# lab3.net
KiCad netlist of a schematic drawn in EAGLE
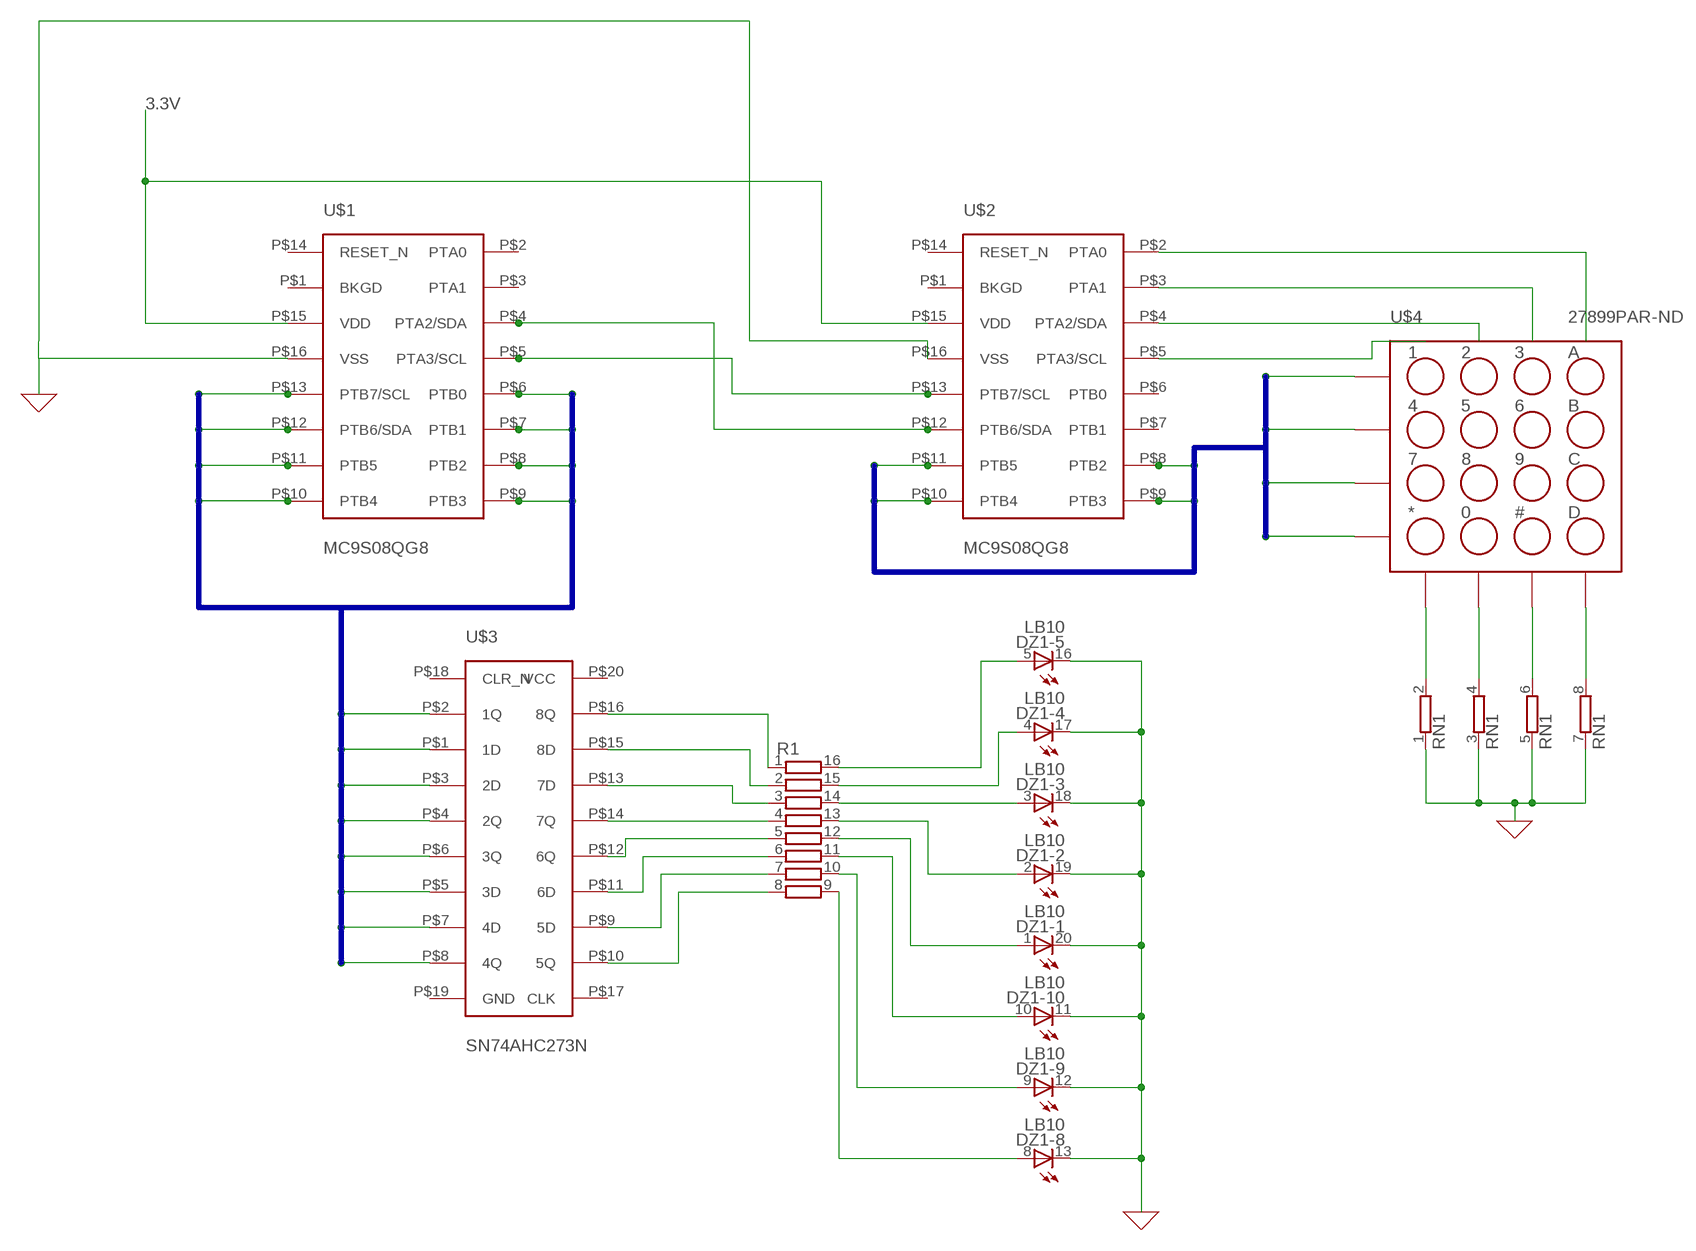
[diagram p0: schematic, sheet 1]

(export (version "E")
  (design (tool "Eeschema 10.0.6"))
  (components
    (comp (ref "DZ1")
      (value "LB10")
      (footprint "eagle-import:LB10")
      (libsource (lib "eagle-import") (part "LB10"))
    )
    (comp (ref "R1")
      (value "2QSP16-8")
      (footprint "eagle-import:2QSP16")
      (libsource (lib "eagle-import") (part "2QSP16-8"))
    )
    (comp (ref "RN1")
      (value "E4RP")
      (footprint "eagle-import:SIL8")
      (libsource (lib "eagle-import") (part "E4RP"))
    )
    (comp (ref "U$1")
      (value "MC9S08QG8")
      (footprint "eagle-import:MC9S08QG8")
      (libsource (lib "eagle-import") (part "MC9S08QG8"))
    )
    (comp (ref "U$2")
      (value "MC9S08QG8")
      (footprint "eagle-import:MC9S08QG8")
      (libsource (lib "eagle-import") (part "MC9S08QG8"))
    )
    (comp (ref "U$3")
      (value "SN74AHC273N")
      (footprint "eagle-import:SN74AHC273N")
      (libsource (lib "eagle-import") (part "SN74AHC273N"))
    )
    (comp (ref "U$4")
      (value "27899PAR-ND")
      (footprint "eagle-import:27899PAR-ND")
      (libsource (lib "eagle-import") (part "27899PAR-ND"))
    )
  )
  (nets
    (net (code "1") (name "/3.3V") (class "Default")
      (node (ref "U$1") (pin "P$15") (pinfunction "VDD_P$15") (pintype "bidirectional"))
      (node (ref "U$2") (pin "P$15") (pinfunction "VDD_P$15") (pintype "bidirectional"))
    )
    (net (code "2") (name "GND") (class "Default")
      (node (ref "DZ1") (pin "11") (pinfunction "C_11") (pintype "passive"))
      (node (ref "DZ1") (pin "12") (pinfunction "C_12") (pintype "passive"))
      (node (ref "DZ1") (pin "13") (pinfunction "C_13") (pintype "passive"))
      (node (ref "DZ1") (pin "16") (pinfunction "C_16") (pintype "passive"))
      (node (ref "DZ1") (pin "17") (pinfunction "C_17") (pintype "passive"))
      (node (ref "DZ1") (pin "18") (pinfunction "C_18") (pintype "passive"))
      (node (ref "DZ1") (pin "19") (pinfunction "C_19") (pintype "passive"))
      (node (ref "DZ1") (pin "20") (pinfunction "C_20") (pintype "passive"))
      (node (ref "RN1") (pin "1") (pinfunction "1_1") (pintype "passive"))
      (node (ref "RN1") (pin "3") (pinfunction "1_3") (pintype "passive"))
      (node (ref "RN1") (pin "5") (pinfunction "1_5") (pintype "passive"))
      (node (ref "RN1") (pin "7") (pinfunction "1_7") (pintype "passive"))
      (node (ref "U$1") (pin "P$16") (pinfunction "VSS_P$16") (pintype "bidirectional"))
      (node (ref "U$2") (pin "P$16") (pinfunction "VSS_P$16") (pintype "bidirectional"))
    )
    (net (code "3") (name "Net-(DZ1A-A)") (class "Default")
      (node (ref "DZ1") (pin "1") (pinfunction "A_1") (pintype "passive"))
      (node (ref "R1") (pin "12") (pinfunction "12_12") (pintype "passive"))
    )
    (net (code "4") (name "Net-(DZ1B-A)") (class "Default")
      (node (ref "DZ1") (pin "10") (pinfunction "A_10") (pintype "passive"))
      (node (ref "R1") (pin "11") (pinfunction "11_11") (pintype "passive"))
    )
    (net (code "5") (name "Net-(DZ1C-A)") (class "Default")
      (node (ref "DZ1") (pin "2") (pinfunction "A_2") (pintype "passive"))
      (node (ref "R1") (pin "13") (pinfunction "13_13") (pintype "passive"))
    )
    (net (code "6") (name "Net-(DZ1D-A)") (class "Default")
      (node (ref "DZ1") (pin "3") (pinfunction "A_3") (pintype "passive"))
      (node (ref "R1") (pin "14") (pinfunction "14_14") (pintype "passive"))
    )
    (net (code "7") (name "Net-(DZ1E-A)") (class "Default")
      (node (ref "DZ1") (pin "4") (pinfunction "A_4") (pintype "passive"))
      (node (ref "R1") (pin "15") (pinfunction "15_15") (pintype "passive"))
    )
    (net (code "8") (name "Net-(DZ1F-A)") (class "Default")
      (node (ref "DZ1") (pin "5") (pinfunction "A_5") (pintype "passive"))
      (node (ref "R1") (pin "16") (pinfunction "16_16") (pintype "passive"))
    )
    (net (code "9") (name "Net-(DZ1I-A)") (class "Default")
      (node (ref "DZ1") (pin "8") (pinfunction "A_8") (pintype "passive"))
      (node (ref "R1") (pin "9") (pinfunction "9_9") (pintype "passive"))
    )
    (net (code "10") (name "Net-(DZ1J-A)") (class "Default")
      (node (ref "DZ1") (pin "9") (pinfunction "A_9") (pintype "passive"))
      (node (ref "R1") (pin "10") (pinfunction "10_10") (pintype "passive"))
    )
    (net (code "11") (name "Net-(RN1-Pad2)") (class "Default")
      (node (ref "RN1") (pin "2") (pinfunction "2_2") (pintype "passive"))
      (node (ref "U$4") (pin "P$8") (pinfunction "P$8_P$8") (pintype "bidirectional"))
    )
    (net (code "12") (name "Net-(RN1B-2)") (class "Default")
      (node (ref "RN1") (pin "4") (pinfunction "2_4") (pintype "passive"))
      (node (ref "U$4") (pin "P$7") (pinfunction "P$7_P$7") (pintype "bidirectional"))
    )
    (net (code "13") (name "Net-(RN1C-2)") (class "Default")
      (node (ref "RN1") (pin "6") (pinfunction "2_6") (pintype "passive"))
      (node (ref "U$4") (pin "P$6") (pinfunction "P$6_P$6") (pintype "bidirectional"))
    )
    (net (code "14") (name "Net-(RN1D-2)") (class "Default")
      (node (ref "RN1") (pin "8") (pinfunction "2_8") (pintype "passive"))
      (node (ref "U$4") (pin "P$5") (pinfunction "P$5_P$5") (pintype "bidirectional"))
    )
    (net (code "15") (name "Net-(U$1-PTA2{slash}SDA)") (class "Default")
      (node (ref "U$1") (pin "P$4") (pinfunction "PTA2/SDA_P$4") (pintype "bidirectional"))
      (node (ref "U$2") (pin "P$12") (pinfunction "PTB6/SDA_P$12") (pintype "bidirectional"))
    )
    (net (code "16") (name "Net-(U$1-PTA3{slash}SCL)") (class "Default")
      (node (ref "U$1") (pin "P$5") (pinfunction "PTA3/SCL_P$5") (pintype "bidirectional"))
      (node (ref "U$2") (pin "P$13") (pinfunction "PTB7/SCL_P$13") (pintype "bidirectional"))
    )
    (net (code "17") (name "Net-(U$3-5D)") (class "Default")
      (node (ref "R1") (pin "7") (pinfunction "7_7") (pintype "passive"))
      (node (ref "U$3") (pin "P$9") (pinfunction "5D_P$9") (pintype "bidirectional"))
    )
    (net (code "18") (name "Net-(U$3-5Q)") (class "Default")
      (node (ref "R1") (pin "8") (pinfunction "8_8") (pintype "passive"))
      (node (ref "U$3") (pin "P$10") (pinfunction "5Q_P$10") (pintype "bidirectional"))
    )
    (net (code "19") (name "Net-(U$3-6D)") (class "Default")
      (node (ref "R1") (pin "6") (pinfunction "6_6") (pintype "passive"))
      (node (ref "U$3") (pin "P$11") (pinfunction "6D_P$11") (pintype "bidirectional"))
    )
    (net (code "20") (name "Net-(U$3-6Q)") (class "Default")
      (node (ref "R1") (pin "5") (pinfunction "5_5") (pintype "passive"))
      (node (ref "U$3") (pin "P$12") (pinfunction "6Q_P$12") (pintype "bidirectional"))
    )
    (net (code "21") (name "Net-(U$3-7D)") (class "Default")
      (node (ref "R1") (pin "3") (pinfunction "3_3") (pintype "passive"))
      (node (ref "U$3") (pin "P$13") (pinfunction "7D_P$13") (pintype "bidirectional"))
    )
    (net (code "22") (name "Net-(U$3-7Q)") (class "Default")
      (node (ref "R1") (pin "4") (pinfunction "4_4") (pintype "passive"))
      (node (ref "U$3") (pin "P$14") (pinfunction "7Q_P$14") (pintype "bidirectional"))
    )
    (net (code "23") (name "Net-(U$3-8D)") (class "Default")
      (node (ref "R1") (pin "2") (pinfunction "2_2") (pintype "passive"))
      (node (ref "U$3") (pin "P$15") (pinfunction "8D_P$15") (pintype "bidirectional"))
    )
    (net (code "24") (name "Net-(U$3-8Q)") (class "Default")
      (node (ref "R1") (pin "1") (pinfunction "1_1") (pintype "passive"))
      (node (ref "U$3") (pin "P$16") (pinfunction "8Q_P$16") (pintype "bidirectional"))
    )
    (net (code "25") (name "unconnected-(U$1-BKGD-PadP$1)") (class "Default")
      (node (ref "U$1") (pin "P$1") (pinfunction "BKGD_P$1") (pintype "bidirectional"))
    )
    (net (code "26") (name "unconnected-(U$1-PTA0-PadP$2)") (class "Default")
      (node (ref "U$1") (pin "P$2") (pinfunction "PTA0_P$2") (pintype "bidirectional"))
    )
    (net (code "27") (name "unconnected-(U$1-PTA1-PadP$3)") (class "Default")
      (node (ref "U$1") (pin "P$3") (pinfunction "PTA1_P$3") (pintype "bidirectional"))
    )
    (net (code "28") (name "unconnected-(U$1-PTB0-PadP$6)") (class "Default")
      (node (ref "U$1") (pin "P$6") (pinfunction "PTB0_P$6") (pintype "bidirectional"))
    )
    (net (code "29") (name "unconnected-(U$1-PTB1-PadP$7)") (class "Default")
      (node (ref "U$1") (pin "P$7") (pinfunction "PTB1_P$7") (pintype "bidirectional"))
    )
    (net (code "30") (name "unconnected-(U$1-PTB2-PadP$8)") (class "Default")
      (node (ref "U$1") (pin "P$8") (pinfunction "PTB2_P$8") (pintype "bidirectional"))
    )
    (net (code "31") (name "unconnected-(U$1-PTB3-PadP$9)") (class "Default")
      (node (ref "U$1") (pin "P$9") (pinfunction "PTB3_P$9") (pintype "bidirectional"))
    )
    (net (code "32") (name "unconnected-(U$1-PTB4-PadP$10)") (class "Default")
      (node (ref "U$1") (pin "P$10") (pinfunction "PTB4_P$10") (pintype "bidirectional"))
    )
    (net (code "33") (name "unconnected-(U$1-PTB5-PadP$11)") (class "Default")
      (node (ref "U$1") (pin "P$11") (pinfunction "PTB5_P$11") (pintype "bidirectional"))
    )
    (net (code "34") (name "unconnected-(U$1-PTB6{slash}SDA-PadP$12)") (class "Default")
      (node (ref "U$1") (pin "P$12") (pinfunction "PTB6/SDA_P$12") (pintype "bidirectional"))
    )
    (net (code "35") (name "unconnected-(U$1-PTB7{slash}SCL-PadP$13)") (class "Default")
      (node (ref "U$1") (pin "P$13") (pinfunction "PTB7/SCL_P$13") (pintype "bidirectional"))
    )
    (net (code "36") (name "unconnected-(U$1-RESET_N-PadP$14)") (class "Default")
      (node (ref "U$1") (pin "P$14") (pinfunction "RESET_N_P$14") (pintype "bidirectional"))
    )
    (net (code "37") (name "unconnected-(U$2-BKGD-PadP$1)") (class "Default")
      (node (ref "U$2") (pin "P$1") (pinfunction "BKGD_P$1") (pintype "bidirectional"))
    )
    (net (code "38") (name "unconnected-(U$2-PTA0-PadP$2)") (class "Default")
      (node (ref "U$2") (pin "P$2") (pinfunction "PTA0_P$2") (pintype "bidirectional"))
    )
    (net (code "39") (name "unconnected-(U$2-PTA1-PadP$3)") (class "Default")
      (node (ref "U$2") (pin "P$3") (pinfunction "PTA1_P$3") (pintype "bidirectional"))
    )
    (net (code "40") (name "unconnected-(U$2-PTA2{slash}SDA-PadP$4)") (class "Default")
      (node (ref "U$2") (pin "P$4") (pinfunction "PTA2/SDA_P$4") (pintype "bidirectional"))
    )
    (net (code "41") (name "unconnected-(U$2-PTA3{slash}SCL-PadP$5)") (class "Default")
      (node (ref "U$2") (pin "P$5") (pinfunction "PTA3/SCL_P$5") (pintype "bidirectional"))
    )
    (net (code "42") (name "unconnected-(U$2-PTB0-PadP$6)") (class "Default")
      (node (ref "U$2") (pin "P$6") (pinfunction "PTB0_P$6") (pintype "bidirectional"))
    )
    (net (code "43") (name "unconnected-(U$2-PTB1-PadP$7)") (class "Default")
      (node (ref "U$2") (pin "P$7") (pinfunction "PTB1_P$7") (pintype "bidirectional"))
    )
    (net (code "44") (name "unconnected-(U$2-PTB2-PadP$8)") (class "Default")
      (node (ref "U$2") (pin "P$8") (pinfunction "PTB2_P$8") (pintype "bidirectional"))
    )
    (net (code "45") (name "unconnected-(U$2-PTB3-PadP$9)") (class "Default")
      (node (ref "U$2") (pin "P$9") (pinfunction "PTB3_P$9") (pintype "bidirectional"))
    )
    (net (code "46") (name "unconnected-(U$2-PTB4-PadP$10)") (class "Default")
      (node (ref "U$2") (pin "P$10") (pinfunction "PTB4_P$10") (pintype "bidirectional"))
    )
    (net (code "47") (name "unconnected-(U$2-PTB5-PadP$11)") (class "Default")
      (node (ref "U$2") (pin "P$11") (pinfunction "PTB5_P$11") (pintype "bidirectional"))
    )
    (net (code "48") (name "unconnected-(U$2-RESET_N-PadP$14)") (class "Default")
      (node (ref "U$2") (pin "P$14") (pinfunction "RESET_N_P$14") (pintype "bidirectional"))
    )
    (net (code "49") (name "unconnected-(U$3-1D-PadP$1)") (class "Default")
      (node (ref "U$3") (pin "P$1") (pinfunction "1D_P$1") (pintype "bidirectional"))
    )
    (net (code "50") (name "unconnected-(U$3-1Q-PadP$2)") (class "Default")
      (node (ref "U$3") (pin "P$2") (pinfunction "1Q_P$2") (pintype "bidirectional"))
    )
    (net (code "51") (name "unconnected-(U$3-2D-PadP$3)") (class "Default")
      (node (ref "U$3") (pin "P$3") (pinfunction "2D_P$3") (pintype "bidirectional"))
    )
    (net (code "52") (name "unconnected-(U$3-2Q-PadP$4)") (class "Default")
      (node (ref "U$3") (pin "P$4") (pinfunction "2Q_P$4") (pintype "bidirectional"))
    )
    (net (code "53") (name "unconnected-(U$3-3D-PadP$5)") (class "Default")
      (node (ref "U$3") (pin "P$5") (pinfunction "3D_P$5") (pintype "bidirectional"))
    )
    (net (code "54") (name "unconnected-(U$3-3Q-PadP$6)") (class "Default")
      (node (ref "U$3") (pin "P$6") (pinfunction "3Q_P$6") (pintype "bidirectional"))
    )
    (net (code "55") (name "unconnected-(U$3-4D-PadP$7)") (class "Default")
      (node (ref "U$3") (pin "P$7") (pinfunction "4D_P$7") (pintype "bidirectional"))
    )
    (net (code "56") (name "unconnected-(U$3-4Q-PadP$8)") (class "Default")
      (node (ref "U$3") (pin "P$8") (pinfunction "4Q_P$8") (pintype "bidirectional"))
    )
    (net (code "57") (name "unconnected-(U$3-CLK-PadP$17)") (class "Default")
      (node (ref "U$3") (pin "P$17") (pinfunction "CLK_P$17") (pintype "bidirectional"))
    )
    (net (code "58") (name "unconnected-(U$3-CLR_N-PadP$18)") (class "Default")
      (node (ref "U$3") (pin "P$18") (pinfunction "CLR_N_P$18") (pintype "bidirectional"))
    )
    (net (code "59") (name "unconnected-(U$3-GND-PadP$19)") (class "Default")
      (node (ref "U$3") (pin "P$19") (pinfunction "GND_P$19") (pintype "bidirectional"))
    )
    (net (code "60") (name "unconnected-(U$3-VCC-PadP$20)") (class "Default")
      (node (ref "U$3") (pin "P$20") (pinfunction "VCC_P$20") (pintype "bidirectional"))
    )
    (net (code "61") (name "unconnected-(U$4-PadP$1)") (class "Default")
      (node (ref "U$4") (pin "P$1") (pinfunction "P$1_P$1") (pintype "bidirectional"))
    )
    (net (code "62") (name "unconnected-(U$4-PadP$2)") (class "Default")
      (node (ref "U$4") (pin "P$2") (pinfunction "P$2_P$2") (pintype "bidirectional"))
    )
    (net (code "63") (name "unconnected-(U$4-PadP$3)") (class "Default")
      (node (ref "U$4") (pin "P$3") (pinfunction "P$3_P$3") (pintype "bidirectional"))
    )
    (net (code "64") (name "unconnected-(U$4-PadP$4)") (class "Default")
      (node (ref "U$4") (pin "P$4") (pinfunction "P$4_P$4") (pintype "bidirectional"))
    )
  )
)
